# Power_InrushLimit.net
KiCad netlist of a schematic drawn in Altium Designer
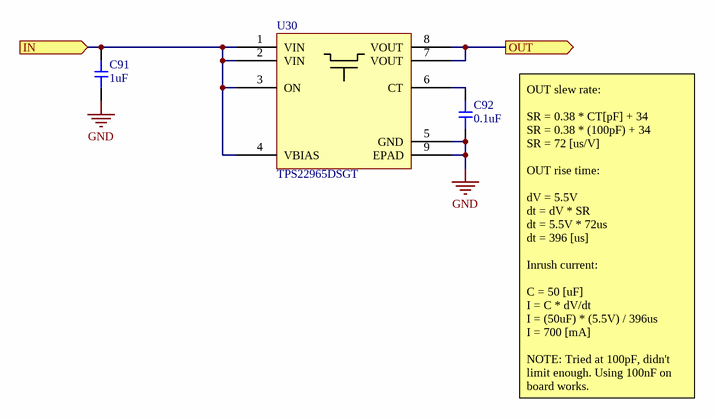
[diagram p0: Power_InrushLimit.SchDoc]

(export (version "E")
  (design (tool "Eeschema 10.0.6"))
  (components
    (comp (ref "C91")
      (value "1uF")
      (footprint "0603-CAP")
      (description "Capacitor")
      (libsource (lib "AMDC") (part "Capacitor"))
    )
    (comp (ref "C92")
      (value "0.1uF")
      (footprint "0603-CAP")
      (description "Capacitor")
      (libsource (lib "AMDC") (part "Capacitor"))
    )
    (comp (ref "U30")
      (value "TPS22965DSGT")
      (footprint "SON50P200X80_HS-9N")
      (description "IC LOAD SWITCH 6A 8WSON")
      (libsource (lib "AMDC") (part "TPS22965DSGT"))
    )
  )
  (nets
    (net (code "1") (name "/IN") (class "Default")
      (node (ref "C91") (pin "2") (pinfunction "2_2") (pintype "passive"))
      (node (ref "U30") (pin "1") (pinfunction "VIN_1") (pintype "passive"))
      (node (ref "U30") (pin "2") (pinfunction "VIN_2") (pintype "passive"))
      (node (ref "U30") (pin "3") (pinfunction "ON_3") (pintype "passive"))
      (node (ref "U30") (pin "4") (pinfunction "VBIAS_4") (pintype "passive"))
    )
    (net (code "2") (name "/OUT") (class "Default")
      (node (ref "U30") (pin "7") (pinfunction "VOUT_7") (pintype "passive"))
      (node (ref "U30") (pin "8") (pinfunction "VOUT_8") (pintype "passive"))
    )
    (net (code "3") (name "GND") (class "Default")
      (node (ref "C91") (pin "1") (pinfunction "1_1") (pintype "passive"))
      (node (ref "C92") (pin "1") (pinfunction "1_1") (pintype "passive"))
      (node (ref "U30") (pin "5") (pinfunction "GND_5") (pintype "passive"))
      (node (ref "U30") (pin "9") (pinfunction "EPAD_9") (pintype "passive"))
    )
    (net (code "4") (name "Net-(U30-CT)") (class "Default")
      (node (ref "C92") (pin "2") (pinfunction "2_2") (pintype "passive"))
      (node (ref "U30") (pin "6") (pinfunction "CT_6") (pintype "passive"))
    )
  )
)
